# My_design_2025-04-12.net
KiCad netlist of a schematic drawn in EasyEDA Pro
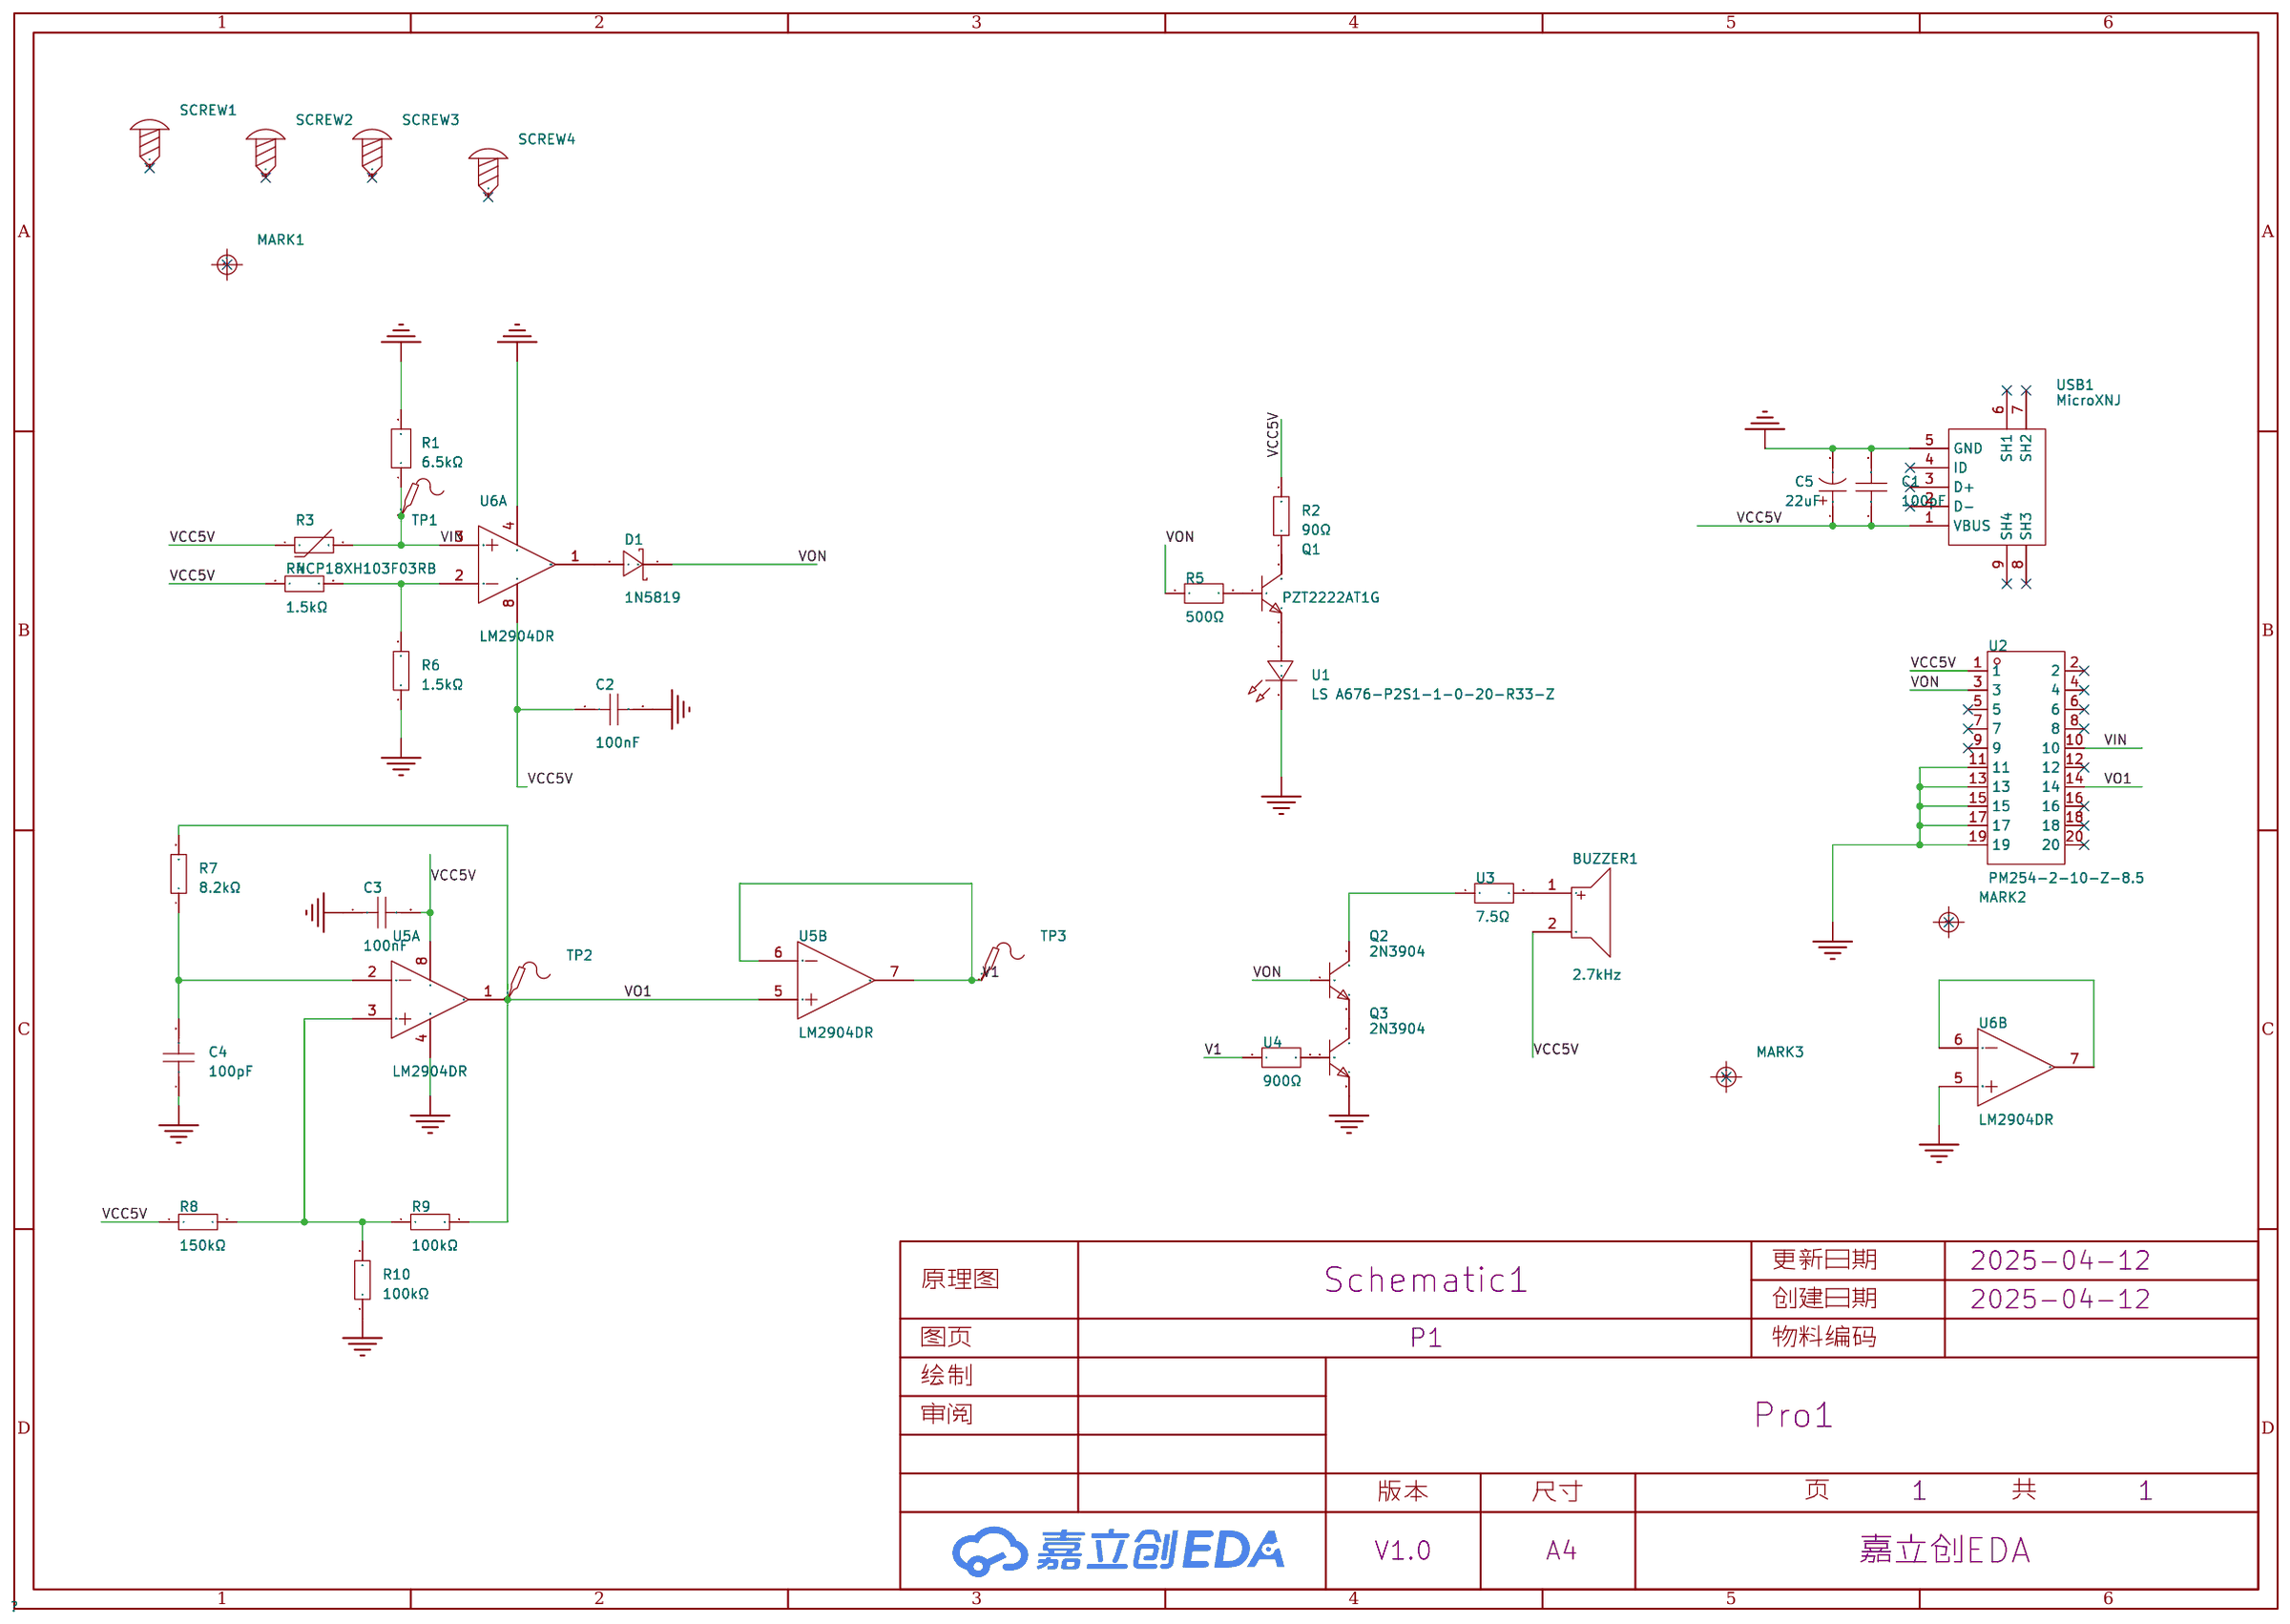
[diagram p0: schematic sheet]

(export (version "E")
  (design (tool "Eeschema 10.0.6"))
  (components
    (comp (ref "BUZZER1")
      (value "2.7kHz")
      (footprint "easyedapro:BUZ-TH_BD9.0-P4.00-D0.6-FD")
      (description "驱动方式:无源(外部驱动);构造类型:电磁式;频率:2.7kHz;声压(SPL):85dB@3V,10cm;")
      (fields (field (name "Manufacturer Part") "QMB-09B-03") (field (name "Manufacturer") "华能"))
      (libsource (lib "easyedapro") (part "QMB-09B-03"))
    )
    (comp (ref "C1")
      (value "100pF")
      (footprint "easyedapro:C0603")
      (description "容值:100pF;精度:±5%;额定电压:50V;材质(温度系数):NP0;")
      (fields
        (field (name "Manufacturer Part") "CC0603JRNPO9BN101")
        (field (name "Manufacturer") "YAGEO(国巨)")
      )
      (libsource (lib "easyedapro") (part "CC0603JRNPO9BN101"))
    )
    (comp (ref "C2")
      (value "100nF")
      (footprint "easyedapro:C0603")
      (description "容值:100nF;精度:±10%;额定电压:50V;材质(温度系数):X7R;")
      (fields
        (field (name "Manufacturer Part") "CC0603KRX7R9BB104")
        (field (name "Manufacturer") "YAGEO(国巨)")
      )
      (libsource (lib "easyedapro") (part "CC0603KRX7R9BB104"))
    )
    (comp (ref "C3")
      (value "100nF")
      (footprint "easyedapro:C0603")
      (description "容值:100nF;精度:±10%;额定电压:50V;材质(温度系数):X7R;")
      (fields
        (field (name "Manufacturer Part") "CC0603KRX7R9BB104")
        (field (name "Manufacturer") "YAGEO(国巨)")
      )
      (libsource (lib "easyedapro") (part "CC0603KRX7R9BB104"))
    )
    (comp (ref "C4")
      (value "100pF")
      (footprint "easyedapro:C0603")
      (description "容值:100pF;精度:±5%;额定电压:50V;材质(温度系数):NP0;")
      (fields
        (field (name "Manufacturer Part") "CC0603JRNPO9BN101")
        (field (name "Manufacturer") "YAGEO(国巨)")
      )
      (libsource (lib "easyedapro") (part "CC0603JRNPO9BN101"))
    )
    (comp (ref "C5")
      (value "22uF")
      (footprint "easyedapro:CAP-TH_BD8.0-P5.00-D0.6-FD")
      (description "容值:22uF;额定电压:400V;")
      (fields
        (field (name "Manufacturer Part") "CD110226M2G0816VFL")
        (field (name "Manufacturer") "HRK(鸿瑞凯)")
      )
      (libsource (lib "easyedapro") (part "CD110226M2G0816VFL"))
    )
    (comp (ref "D1")
      (value "1N5819")
      (footprint "easyedapro:SMA_L4.4-W2.6-LS5.0-RD")
      (description "正向压降(Vf):500mV@1A;直流反向耐压(Vr):40V;平均整流电流(Io):1A;")
      (fields (field (name "Manufacturer") "KEXIN(科信)"))
      (libsource (lib "easyedapro") (part "1N5819_C437199"))
    )
    (comp (ref "MARK1")
      (value "~")
      (footprint "easyedapro:Mark-Point-1mm")
      (description "Mark点")
      (libsource (lib "easyedapro") (part "Mark-Point"))
    )
    (comp (ref "MARK2")
      (value "~")
      (footprint "easyedapro:Mark-Point-1mm")
      (description "Mark点")
      (libsource (lib "easyedapro") (part "Mark-Point"))
    )
    (comp (ref "MARK3")
      (value "~")
      (footprint "easyedapro:Mark-Point-1mm")
      (description "Mark点")
      (libsource (lib "easyedapro") (part "Mark-Point"))
    )
    (comp (ref "Q1")
      (value "PZT2222AT1G")
      (footprint "easyedapro:SOT-223_L6.5-W3.5-P2.30-LS7.0-BR")
      (description "晶体管类型:NPN;集电极电流(Ic):600mA;集射极击穿电压(Vceo):40V;功率(Pd):1.5W;直流电流增益(hFE@Ic,Vce):35@150mA,10V;")
      (fields (field (name "Manufacturer") "onsemi(安森美)"))
      (libsource (lib "easyedapro") (part "PZT2222AT1G"))
    )
    (comp (ref "Q2")
      (value "2N3904")
      (footprint "easyedapro:TO-92-3_L4.6-W3.6-P1.27-L_1")
      (description "晶体管类型:NPN;集电极电流(Ic):200mA;集射极击穿电压(Vceo):40V;功率(Pd):625mW;直流电流增益(hFE@Ic,Vce):10@10mA,1V;")
      (fields (field (name "Manufacturer") "JSMSEMI(杰盛微)"))
      (libsource (lib "easyedapro") (part "2N3904_C2874602"))
    )
    (comp (ref "Q3")
      (value "2N3904")
      (footprint "easyedapro:TO-92-3_L4.6-W3.6-P1.27-L_1")
      (description "晶体管类型:NPN;集电极电流(Ic):200mA;集射极击穿电压(Vceo):40V;功率(Pd):625mW;直流电流增益(hFE@Ic,Vce):10@10mA,1V;")
      (fields (field (name "Manufacturer") "JSMSEMI(杰盛微)"))
      (libsource (lib "easyedapro") (part "2N3904_C2874602"))
    )
    (comp (ref "R1")
      (value "6.5kΩ")
      (footprint "easyedapro:R0603")
      (description "电阻类型:薄膜电阻;阻值:6.5kΩ;精度:±0.1%;功率:100mW;最大工作电压:75V;温度系数:±25ppm/°C;")
      (fields
        (field (name "Manufacturer Part") "MCT06030D6501BP100")
        (field (name "Manufacturer") "VISHAY(威世)")
      )
      (libsource (lib "easyedapro") (part "MCT06030D6501BP100"))
    )
    (comp (ref "R2")
      (value "90Ω")
      (footprint "easyedapro:R0805")
      (description "电阻类型:厚膜电阻;阻值:90Ω;精度:±1%;功率:125mW;最大工作电压:150V;温度系数:±100ppm/°C;")
      (fields (field (name "Manufacturer Part") "RS-05K90R0FT") (field (name "Manufacturer") "FH(风华)"))
      (libsource (lib "easyedapro") (part "RS-05K90R0FT"))
    )
    (comp (ref "R3")
      (value "NCP18XH103F03RB")
      (footprint "easyedapro:R0603")
      (description "阻值(25°C):10kΩ;B值(25°C/50°C):3380K;电阻精度:±1%;功率:100mW;B值精度:±1%;最大稳态电流(25°C):310uA;")
      (fields (field (name "Manufacturer") "muRata(村田)"))
      (libsource (lib "easyedapro") (part "NCP18XH103F03RB"))
    )
    (comp (ref "R4")
      (value "1.5kΩ")
      (footprint "easyedapro:R0603")
      (description "电阻类型:厚膜电阻;阻值:1.5kΩ;精度:±1%;功率:100mW;最大工作电压:75V;温度系数:±100ppm/°C;")
      (fields
        (field (name "Manufacturer Part") "0603WAF1501T5E")
        (field (name "Manufacturer") "UNI-ROYAL(厚声)")
      )
      (libsource (lib "easyedapro") (part "0603WAF1501T5E"))
    )
    (comp (ref "R5")
      (value "500Ω")
      (footprint "easyedapro:R0805")
      (description "电阻类型:薄膜电阻;阻值:500Ω;精度:±1%;功率:125mW;最大工作电压:150V;温度系数:±25ppm/°C;")
      (fields (field (name "Manufacturer Part") "ARG05FTC5000") (field (name "Manufacturer") "Viking(光颉)"))
      (libsource (lib "easyedapro") (part "ARG05FTC5000"))
    )
    (comp (ref "R6")
      (value "1.5kΩ")
      (footprint "easyedapro:R0603")
      (description "电阻类型:厚膜电阻;阻值:1.5kΩ;精度:±1%;功率:100mW;最大工作电压:75V;温度系数:±100ppm/°C;")
      (fields
        (field (name "Manufacturer Part") "0603WAF1501T5E")
        (field (name "Manufacturer") "UNI-ROYAL(厚声)")
      )
      (libsource (lib "easyedapro") (part "0603WAF1501T5E"))
    )
    (comp (ref "R7")
      (value "8.2kΩ")
      (footprint "easyedapro:R0603")
      (description "电阻类型:厚膜电阻;阻值:8.2kΩ;精度:±1%;功率:100mW;最大工作电压:75V;温度系数:±100ppm/°C;")
      (fields
        (field (name "Manufacturer Part") "0603WAF8201T5E")
        (field (name "Manufacturer") "UNI-ROYAL(厚声)")
      )
      (libsource (lib "easyedapro") (part "0603WAF8201T5E"))
    )
    (comp (ref "R8")
      (value "150kΩ")
      (footprint "easyedapro:R0603")
      (description "电阻类型:厚膜电阻;阻值:150kΩ;精度:±1%;功率:100mW;最大工作电压:75V;温度系数:±100ppm/°C;")
      (fields
        (field (name "Manufacturer Part") "0603WAF1503T5E")
        (field (name "Manufacturer") "UNI-ROYAL(厚声)")
      )
      (libsource (lib "easyedapro") (part "0603WAF1503T5E"))
    )
    (comp (ref "R9")
      (value "100kΩ")
      (footprint "easyedapro:R0603")
      (description "电阻类型:厚膜电阻;阻值:100kΩ;精度:±1%;功率:100mW;最大工作电压:75V;温度系数:±100ppm/°C;")
      (fields
        (field (name "Manufacturer Part") "0603WAF1003T5E")
        (field (name "Manufacturer") "UNI-ROYAL(厚声)")
      )
      (libsource (lib "easyedapro") (part "0603WAF1003T5E"))
    )
    (comp (ref "R10")
      (value "100kΩ")
      (footprint "easyedapro:R0603")
      (description "电阻类型:厚膜电阻;阻值:100kΩ;精度:±1%;功率:100mW;最大工作电压:75V;温度系数:±100ppm/°C;")
      (fields
        (field (name "Manufacturer Part") "0603WAF1003T5E")
        (field (name "Manufacturer") "UNI-ROYAL(厚声)")
      )
      (libsource (lib "easyedapro") (part "0603WAF1003T5E"))
    )
    (comp (ref "SCREW1")
      (value "~")
      (footprint "easyedapro:M3螺丝")
      (libsource (lib "easyedapro") (part "螺丝孔"))
    )
    (comp (ref "SCREW2")
      (value "~")
      (footprint "easyedapro:M3螺丝")
      (libsource (lib "easyedapro") (part "螺丝孔"))
    )
    (comp (ref "SCREW3")
      (value "~")
      (footprint "easyedapro:M3螺丝")
      (libsource (lib "easyedapro") (part "螺丝孔"))
    )
    (comp (ref "SCREW4")
      (value "~")
      (footprint "easyedapro:M3螺丝")
      (libsource (lib "easyedapro") (part "螺丝孔"))
    )
    (comp (ref "TP1")
      (value "~")
      (footprint "easyedapro:Test-Point-0.5mm")
      (description "Test Point 测试点")
      (libsource (lib "easyedapro") (part "Test-Point"))
    )
    (comp (ref "TP2")
      (value "~")
      (footprint "easyedapro:Test-Point-0.5mm")
      (description "Test Point 测试点")
      (libsource (lib "easyedapro") (part "Test-Point"))
    )
    (comp (ref "TP3")
      (value "~")
      (footprint "easyedapro:Test-Point-0.5mm")
      (description "Test Point 测试点")
      (libsource (lib "easyedapro") (part "Test-Point"))
    )
    (comp (ref "U1")
      (value "LS A676-P2S1-1-0-20-R33-Z")
      (footprint "easyedapro:LED-SMD_L4.0-W3.6-P2.54-RD")
      (fields (field (name "Manufacturer") "OSRAM(欧司朗)"))
      (libsource (lib "easyedapro") (part "LS A676-P2S1-1-0-20-R33-Z"))
    )
    (comp (ref "U2")
      (value "PM254-2-10-Z-8.5")
      (footprint "easyedapro:HDR-TH_20P-P2.54-V-F-R2-C10-S2.54")
      (fields (field (name "Manufacturer") "HCTL(华灿天禄)"))
      (libsource (lib "easyedapro") (part "PM254-2-10-Z-8.5"))
    )
    (comp (ref "U3")
      (value "7.5Ω")
      (footprint "easyedapro:R1206")
      (description "电阻类型:厚膜电阻;阻值:7.5Ω;精度:±1%;功率:250mW;最大工作电压:200V;温度系数:±200ppm/°C;")
      (fields (field (name "Manufacturer Part") "FRC1206F7R50TS") (field (name "Manufacturer") "FOJAN(富捷)"))
      (libsource (lib "easyedapro") (part "FRC1206F7R50TS"))
    )
    (comp (ref "U4")
      (value "900Ω")
      (footprint "easyedapro:R0805")
      (description "电阻类型:薄膜电阻;阻值:900Ω;精度:±0.1%;功率:125mW;最大工作电压:150V;温度系数:±25ppm/°C;")
      (fields (field (name "Manufacturer Part") "ARG05BTC9000N") (field (name "Manufacturer") "Viking(光颉)"))
      (libsource (lib "easyedapro") (part "ARG05BTC9000N"))
    )
    (comp (ref "U5")
      (value "LM2904DR")
      (footprint "easyedapro:SOIC-8_L4.9-W3.9-P1.27-LS6.0-BL")
      (description "放大器数:双路;增益带宽积(GBP):700kHz;输入偏置电流(Ib):20nA;压摆率(SR):0.3V/us;带宽(-3db):-;")
      (fields (field (name "Manufacturer") "TI(德州仪器)"))
      (libsource (lib "easyedapro") (part "LM2904DR"))
    )
    (comp (ref "U6")
      (value "LM2904DR")
      (footprint "easyedapro:SOIC-8_L4.9-W3.9-P1.27-LS6.0-BL")
      (description "放大器数:双路;增益带宽积(GBP):700kHz;输入偏置电流(Ib):20nA;压摆率(SR):0.3V/us;带宽(-3db):-;")
      (fields (field (name "Manufacturer") "TI(德州仪器)"))
      (libsource (lib "easyedapro") (part "LM2904DR"))
    )
    (comp (ref "USB1")
      (value "MicroXNJ")
      (footprint "easyedapro:MICRO-USB-SMD_MICROXNJ")
      (description "连接器类型:Micro-B;标准:USB 2.0;公母:母;安装方式:卧贴;触点数量:5P;端口数量:1;额定电流 - 电源:1A;工作温度范围:-20°C~+85°C;")
      (fields (field (name "Manufacturer") "SHOU HAN(首韩)"))
      (libsource (lib "easyedapro") (part "MICROXNJ"))
    )
  )
  (nets
    (net (code "1") (name "/V1") (class "Default")
      (node (ref "TP3") (pin "1") (pinfunction "1_1") (pintype "input"))
      (node (ref "U4") (pin "1") (pinfunction "1_1") (pintype "unspecified"))
      (node (ref "U5") (pin "6") (pinfunction "2IN-_6") (pintype "unspecified"))
      (node (ref "U5") (pin "7") (pinfunction "2OUT_7") (pintype "output"))
    )
    (net (code "2") (name "/VCC5V") (class "Default")
      (node (ref "BUZZER1") (pin "2") (pinfunction "2_2") (pintype "unspecified"))
      (node (ref "C1") (pin "1") (pinfunction "1_1") (pintype "unspecified"))
      (node (ref "C2") (pin "1") (pinfunction "1_1") (pintype "unspecified"))
      (node (ref "C3") (pin "2") (pinfunction "2_2") (pintype "unspecified"))
      (node (ref "C5") (pin "1") (pinfunction "1_1") (pintype "input"))
      (node (ref "R2") (pin "2") (pinfunction "2_2") (pintype "unspecified"))
      (node (ref "R3") (pin "1") (pinfunction "1_1") (pintype "input"))
      (node (ref "R4") (pin "1") (pinfunction "1_1") (pintype "input"))
      (node (ref "R8") (pin "1") (pinfunction "1_1") (pintype "input"))
      (node (ref "U2") (pin "1") (pinfunction "1_1") (pintype "unspecified"))
      (node (ref "U5") (pin "8") (pinfunction "VCC_8") (pintype "unspecified"))
      (node (ref "U6") (pin "8") (pinfunction "VCC_8") (pintype "unspecified"))
      (node (ref "USB1") (pin "1") (pinfunction "VBUS_1") (pintype "unspecified"))
    )
    (net (code "3") (name "/VIN") (class "Default")
      (node (ref "R1") (pin "1") (pinfunction "1_1") (pintype "unspecified"))
      (node (ref "R3") (pin "2") (pinfunction "2_2") (pintype "input"))
      (node (ref "TP1") (pin "1") (pinfunction "1_1") (pintype "input"))
      (node (ref "U2") (pin "10") (pinfunction "10_10") (pintype "unspecified"))
      (node (ref "U6") (pin "3") (pinfunction "1IN+_3") (pintype "unspecified"))
    )
    (net (code "4") (name "/VO1") (class "Default")
      (node (ref "R7") (pin "2") (pinfunction "2_2") (pintype "input"))
      (node (ref "R9") (pin "2") (pinfunction "2_2") (pintype "input"))
      (node (ref "TP2") (pin "1") (pinfunction "1_1") (pintype "input"))
      (node (ref "U2") (pin "14") (pinfunction "14_14") (pintype "unspecified"))
      (node (ref "U5") (pin "1") (pinfunction "1OUT_1") (pintype "output"))
      (node (ref "U5") (pin "5") (pinfunction "2IN+_5") (pintype "unspecified"))
    )
    (net (code "5") (name "/VON") (class "Default")
      (node (ref "D1") (pin "1") (pinfunction "C_1") (pintype "unspecified"))
      (node (ref "Q2") (pin "2") (pinfunction "B_2") (pintype "unspecified"))
      (node (ref "R5") (pin "1") (pinfunction "1_1") (pintype "unspecified"))
      (node (ref "U2") (pin "3") (pinfunction "3_3") (pintype "unspecified"))
    )
    (net (code "6") (name "GND") (class "Default")
      (node (ref "C1") (pin "2") (pinfunction "2_2") (pintype "unspecified"))
      (node (ref "C2") (pin "2") (pinfunction "2_2") (pintype "unspecified"))
      (node (ref "C3") (pin "1") (pinfunction "1_1") (pintype "unspecified"))
      (node (ref "C4") (pin "1") (pinfunction "1_1") (pintype "unspecified"))
      (node (ref "C5") (pin "2") (pinfunction "2_2") (pintype "input"))
      (node (ref "Q3") (pin "3") (pinfunction "E_3") (pintype "unspecified"))
      (node (ref "R1") (pin "2") (pinfunction "2_2") (pintype "unspecified"))
      (node (ref "R10") (pin "1") (pinfunction "1_1") (pintype "input"))
      (node (ref "R6") (pin "1") (pinfunction "1_1") (pintype "input"))
      (node (ref "U1") (pin "1") (pinfunction "C_1") (pintype "unspecified"))
      (node (ref "U2") (pin "11") (pinfunction "11_11") (pintype "unspecified"))
      (node (ref "U2") (pin "13") (pinfunction "13_13") (pintype "unspecified"))
      (node (ref "U2") (pin "15") (pinfunction "15_15") (pintype "unspecified"))
      (node (ref "U2") (pin "17") (pinfunction "17_17") (pintype "unspecified"))
      (node (ref "U2") (pin "19") (pinfunction "19_19") (pintype "unspecified"))
      (node (ref "U5") (pin "4") (pinfunction "GND_4") (pintype "unspecified"))
      (node (ref "U6") (pin "4") (pinfunction "GND_4") (pintype "unspecified"))
      (node (ref "U6") (pin "5") (pinfunction "2IN+_5") (pintype "unspecified"))
      (node (ref "USB1") (pin "5") (pinfunction "GND_5") (pintype "unspecified"))
    )
    (net (code "7") (name "Net-(BUZZER1-Pad1)") (class "Default")
      (node (ref "BUZZER1") (pin "1") (pinfunction "1_1") (pintype "unspecified"))
      (node (ref "U3") (pin "2") (pinfunction "2_2") (pintype "unspecified"))
    )
    (net (code "8") (name "Net-(D1-A)") (class "Default")
      (node (ref "D1") (pin "2") (pinfunction "A_2") (pintype "unspecified"))
      (node (ref "U6") (pin "1") (pinfunction "1OUT_1") (pintype "output"))
    )
    (net (code "9") (name "Net-(Q1-B)") (class "Default")
      (node (ref "Q1") (pin "1") (pinfunction "B_1") (pintype "unspecified"))
      (node (ref "R5") (pin "2") (pinfunction "2_2") (pintype "unspecified"))
    )
    (net (code "10") (name "Net-(Q1-C-Pad2)") (class "Default")
      (node (ref "Q1") (pin "2") (pinfunction "C_2") (pintype "unspecified"))
      (node (ref "Q1") (pin "4") (pinfunction "C_4") (pintype "unspecified"))
      (node (ref "R2") (pin "1") (pinfunction "1_1") (pintype "unspecified"))
    )
    (net (code "11") (name "Net-(Q1-E)") (class "Default")
      (node (ref "Q1") (pin "3") (pinfunction "E_3") (pintype "unspecified"))
      (node (ref "U1") (pin "2") (pinfunction "A_2") (pintype "unspecified"))
    )
    (net (code "12") (name "Net-(Q2-C)") (class "Default")
      (node (ref "Q2") (pin "1") (pinfunction "C_1") (pintype "unspecified"))
      (node (ref "U3") (pin "1") (pinfunction "1_1") (pintype "unspecified"))
    )
    (net (code "13") (name "Net-(Q2-E)") (class "Default")
      (node (ref "Q2") (pin "3") (pinfunction "E_3") (pintype "unspecified"))
      (node (ref "Q3") (pin "1") (pinfunction "C_1") (pintype "unspecified"))
    )
    (net (code "14") (name "Net-(Q3-B)") (class "Default")
      (node (ref "Q3") (pin "2") (pinfunction "B_2") (pintype "unspecified"))
      (node (ref "U4") (pin "2") (pinfunction "2_2") (pintype "unspecified"))
    )
    (net (code "15") (name "Net-(U5A-1IN+)") (class "Default")
      (node (ref "R10") (pin "2") (pinfunction "2_2") (pintype "input"))
      (node (ref "R8") (pin "2") (pinfunction "2_2") (pintype "input"))
      (node (ref "R9") (pin "1") (pinfunction "1_1") (pintype "input"))
      (node (ref "U5") (pin "3") (pinfunction "1IN+_3") (pintype "unspecified"))
    )
    (net (code "16") (name "Net-(U5A-1IN-)") (class "Default")
      (node (ref "C4") (pin "2") (pinfunction "2_2") (pintype "unspecified"))
      (node (ref "R7") (pin "1") (pinfunction "1_1") (pintype "input"))
      (node (ref "U5") (pin "2") (pinfunction "1IN-_2") (pintype "unspecified"))
    )
    (net (code "17") (name "Net-(U6A-1IN-)") (class "Default")
      (node (ref "R4") (pin "2") (pinfunction "2_2") (pintype "input"))
      (node (ref "R6") (pin "2") (pinfunction "2_2") (pintype "input"))
      (node (ref "U6") (pin "2") (pinfunction "1IN-_2") (pintype "unspecified"))
    )
    (net (code "18") (name "Net-(U6B-2IN-)") (class "Default")
      (node (ref "U6") (pin "6") (pinfunction "2IN-_6") (pintype "unspecified"))
      (node (ref "U6") (pin "7") (pinfunction "2OUT_7") (pintype "output"))
    )
    (net (code "19") (name "unconnected-(MARK1-Pad1)") (class "Default")
      (node (ref "MARK1") (pin "1") (pinfunction "1_1") (pintype "input+no_connect"))
    )
    (net (code "20") (name "unconnected-(MARK2-Pad1)") (class "Default")
      (node (ref "MARK2") (pin "1") (pinfunction "1_1") (pintype "input+no_connect"))
    )
    (net (code "21") (name "unconnected-(MARK3-Pad1)") (class "Default")
      (node (ref "MARK3") (pin "1") (pinfunction "1_1") (pintype "input+no_connect"))
    )
    (net (code "22") (name "unconnected-(SCREW1-Pad1)") (class "Default")
      (node (ref "SCREW1") (pin "1") (pinfunction "1_1") (pintype "input+no_connect"))
    )
    (net (code "23") (name "unconnected-(SCREW2-Pad1)") (class "Default")
      (node (ref "SCREW2") (pin "1") (pinfunction "1_1") (pintype "input+no_connect"))
    )
    (net (code "24") (name "unconnected-(SCREW3-Pad1)") (class "Default")
      (node (ref "SCREW3") (pin "1") (pinfunction "1_1") (pintype "input+no_connect"))
    )
    (net (code "25") (name "unconnected-(SCREW4-Pad1)") (class "Default")
      (node (ref "SCREW4") (pin "1") (pinfunction "1_1") (pintype "input+no_connect"))
    )
    (net (code "26") (name "unconnected-(U2-Pad2)") (class "Default")
      (node (ref "U2") (pin "2") (pinfunction "2_2") (pintype "unspecified+no_connect"))
    )
    (net (code "27") (name "unconnected-(U2-Pad4)") (class "Default")
      (node (ref "U2") (pin "4") (pinfunction "4_4") (pintype "unspecified+no_connect"))
    )
    (net (code "28") (name "unconnected-(U2-Pad5)") (class "Default")
      (node (ref "U2") (pin "5") (pinfunction "5_5") (pintype "unspecified+no_connect"))
    )
    (net (code "29") (name "unconnected-(U2-Pad6)") (class "Default")
      (node (ref "U2") (pin "6") (pinfunction "6_6") (pintype "unspecified+no_connect"))
    )
    (net (code "30") (name "unconnected-(U2-Pad7)") (class "Default")
      (node (ref "U2") (pin "7") (pinfunction "7_7") (pintype "unspecified+no_connect"))
    )
    (net (code "31") (name "unconnected-(U2-Pad8)") (class "Default")
      (node (ref "U2") (pin "8") (pinfunction "8_8") (pintype "unspecified+no_connect"))
    )
    (net (code "32") (name "unconnected-(U2-Pad9)") (class "Default")
      (node (ref "U2") (pin "9") (pinfunction "9_9") (pintype "unspecified+no_connect"))
    )
    (net (code "33") (name "unconnected-(U2-Pad12)") (class "Default")
      (node (ref "U2") (pin "12") (pinfunction "12_12") (pintype "unspecified+no_connect"))
    )
    (net (code "34") (name "unconnected-(U2-Pad16)") (class "Default")
      (node (ref "U2") (pin "16") (pinfunction "16_16") (pintype "unspecified+no_connect"))
    )
    (net (code "35") (name "unconnected-(U2-Pad18)") (class "Default")
      (node (ref "U2") (pin "18") (pinfunction "18_18") (pintype "unspecified+no_connect"))
    )
    (net (code "36") (name "unconnected-(U2-Pad20)") (class "Default")
      (node (ref "U2") (pin "20") (pinfunction "20_20") (pintype "unspecified+no_connect"))
    )
    (net (code "37") (name "unconnected-(USB1-D+-Pad3)") (class "Default")
      (node (ref "USB1") (pin "3") (pinfunction "D+_3") (pintype "unspecified+no_connect"))
    )
    (net (code "38") (name "unconnected-(USB1-D--Pad2)") (class "Default")
      (node (ref "USB1") (pin "2") (pinfunction "D-_2") (pintype "unspecified+no_connect"))
    )
    (net (code "39") (name "unconnected-(USB1-ID-Pad4)") (class "Default")
      (node (ref "USB1") (pin "4") (pinfunction "ID_4") (pintype "unspecified+no_connect"))
    )
    (net (code "40") (name "unconnected-(USB1-SH1-Pad6)") (class "Default")
      (node (ref "USB1") (pin "6") (pinfunction "SH1_6") (pintype "unspecified+no_connect"))
    )
    (net (code "41") (name "unconnected-(USB1-SH2-Pad7)") (class "Default")
      (node (ref "USB1") (pin "7") (pinfunction "SH2_7") (pintype "unspecified+no_connect"))
    )
    (net (code "42") (name "unconnected-(USB1-SH3-Pad8)") (class "Default")
      (node (ref "USB1") (pin "8") (pinfunction "SH3_8") (pintype "unspecified+no_connect"))
    )
    (net (code "43") (name "unconnected-(USB1-SH4-Pad9)") (class "Default")
      (node (ref "USB1") (pin "9") (pinfunction "SH4_9") (pintype "unspecified+no_connect"))
    )
  )
)
